# ADXL335_Breakout.net
KiCad netlist of a schematic drawn in EAGLE
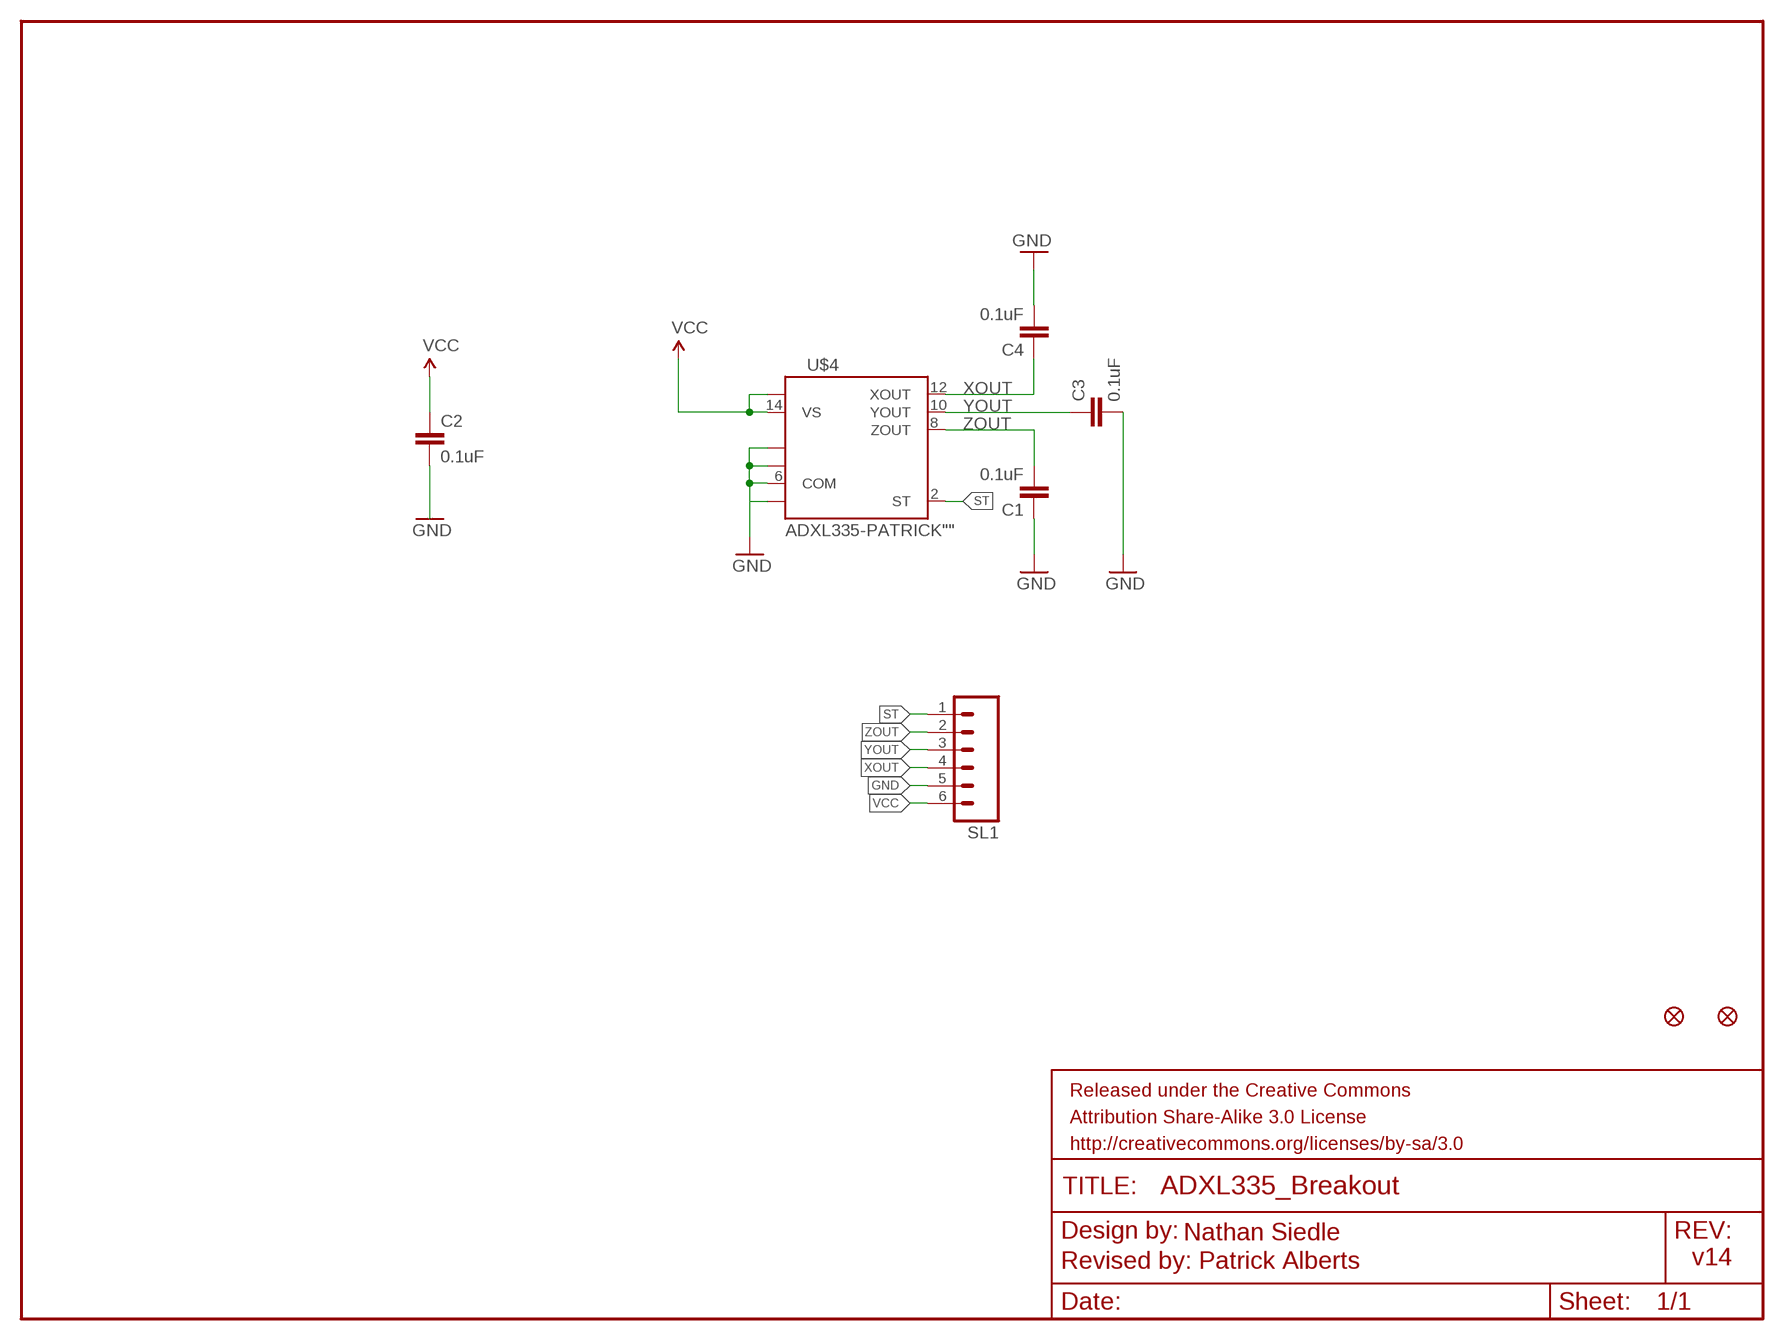
[diagram p0: schematic, sheet 1]

(export (version "E")
  (design (tool "Eeschema 10.0.6"))
  (components
    (comp (ref "C1")
      (value "0.1uF")
      (footprint "eagle-import:0603-CAP")
      (libsource (lib "eagle-import") (part "CAP0603-CAP"))
    )
    (comp (ref "C2")
      (value "0.1uF")
      (footprint "eagle-import:0603-CAP")
      (libsource (lib "eagle-import") (part "CAP0603-CAP"))
    )
    (comp (ref "C3")
      (value "0.1uF")
      (footprint "eagle-import:0603-CAP")
      (libsource (lib "eagle-import") (part "CAP0603-CAP"))
    )
    (comp (ref "C4")
      (value "0.1uF")
      (footprint "eagle-import:0603-CAP")
      (libsource (lib "eagle-import") (part "CAP0603-CAP"))
    )
    (comp (ref "SL1")
      (value "M06SIP")
      (footprint "eagle-import:1X06")
      (libsource (lib "eagle-import") (part "M06SIP"))
    )
    (comp (ref "U$1")
      (value "FIDUCIAL1X2")
      (footprint "eagle-import:FIDUCIAL-1X2")
      (libsource (lib "eagle-import") (part "FIDUCIAL1X2"))
    )
    (comp (ref "U$3")
      (value "FIDUCIAL1X2")
      (footprint "eagle-import:FIDUCIAL-1X2")
      (libsource (lib "eagle-import") (part "FIDUCIAL1X2"))
    )
    (comp (ref "U$4")
      (value "ADXL335-PATRICK\"\"")
      (footprint "eagle-import:ADXL335-P")
      (libsource (lib "eagle-import") (part "ADXL335-PATRICK{dblquote}{dblquote}"))
    )
  )
  (nets
    (net (code "1") (name "GND") (class "Default")
      (node (ref "C1") (pin "1") (pinfunction "1_1") (pintype "passive"))
      (node (ref "C2") (pin "2") (pinfunction "2_2") (pintype "passive"))
      (node (ref "C3") (pin "2") (pinfunction "2_2") (pintype "passive"))
      (node (ref "C4") (pin "2") (pinfunction "2_2") (pintype "passive"))
      (node (ref "SL1") (pin "5") (pinfunction "5_5") (pintype "passive"))
      (node (ref "U$4") (pin "3") (pinfunction "COM_3") (pintype "bidirectional"))
      (node (ref "U$4") (pin "5") (pinfunction "COM_5") (pintype "bidirectional"))
      (node (ref "U$4") (pin "6") (pinfunction "COM_6") (pintype "bidirectional"))
      (node (ref "U$4") (pin "7") (pinfunction "COM_7") (pintype "bidirectional"))
    )
    (net (code "2") (name "ST") (class "Default")
      (node (ref "SL1") (pin "1") (pinfunction "1_1") (pintype "passive"))
      (node (ref "U$4") (pin "2") (pinfunction "ST_2") (pintype "bidirectional"))
    )
    (net (code "3") (name "VCC") (class "Default")
      (node (ref "C2") (pin "1") (pinfunction "1_1") (pintype "passive"))
      (node (ref "SL1") (pin "6") (pinfunction "6_6") (pintype "passive"))
      (node (ref "U$4") (pin "14") (pinfunction "VS_14") (pintype "bidirectional"))
      (node (ref "U$4") (pin "15") (pinfunction "VS_15") (pintype "bidirectional"))
    )
    (net (code "4") (name "XOUT") (class "Default")
      (node (ref "C4") (pin "1") (pinfunction "1_1") (pintype "passive"))
      (node (ref "SL1") (pin "4") (pinfunction "4_4") (pintype "passive"))
      (node (ref "U$4") (pin "12") (pinfunction "XOUT_12") (pintype "bidirectional"))
    )
    (net (code "5") (name "YOUT") (class "Default")
      (node (ref "C3") (pin "1") (pinfunction "1_1") (pintype "passive"))
      (node (ref "SL1") (pin "3") (pinfunction "3_3") (pintype "passive"))
      (node (ref "U$4") (pin "10") (pinfunction "YOUT_10") (pintype "bidirectional"))
    )
    (net (code "6") (name "ZOUT") (class "Default")
      (node (ref "C1") (pin "2") (pinfunction "2_2") (pintype "passive"))
      (node (ref "SL1") (pin "2") (pinfunction "2_2") (pintype "passive"))
      (node (ref "U$4") (pin "8") (pinfunction "ZOUT_8") (pintype "bidirectional"))
    )
  )
)
